# 1_P1.net
KiCad netlist of a schematic drawn in Altium Designer
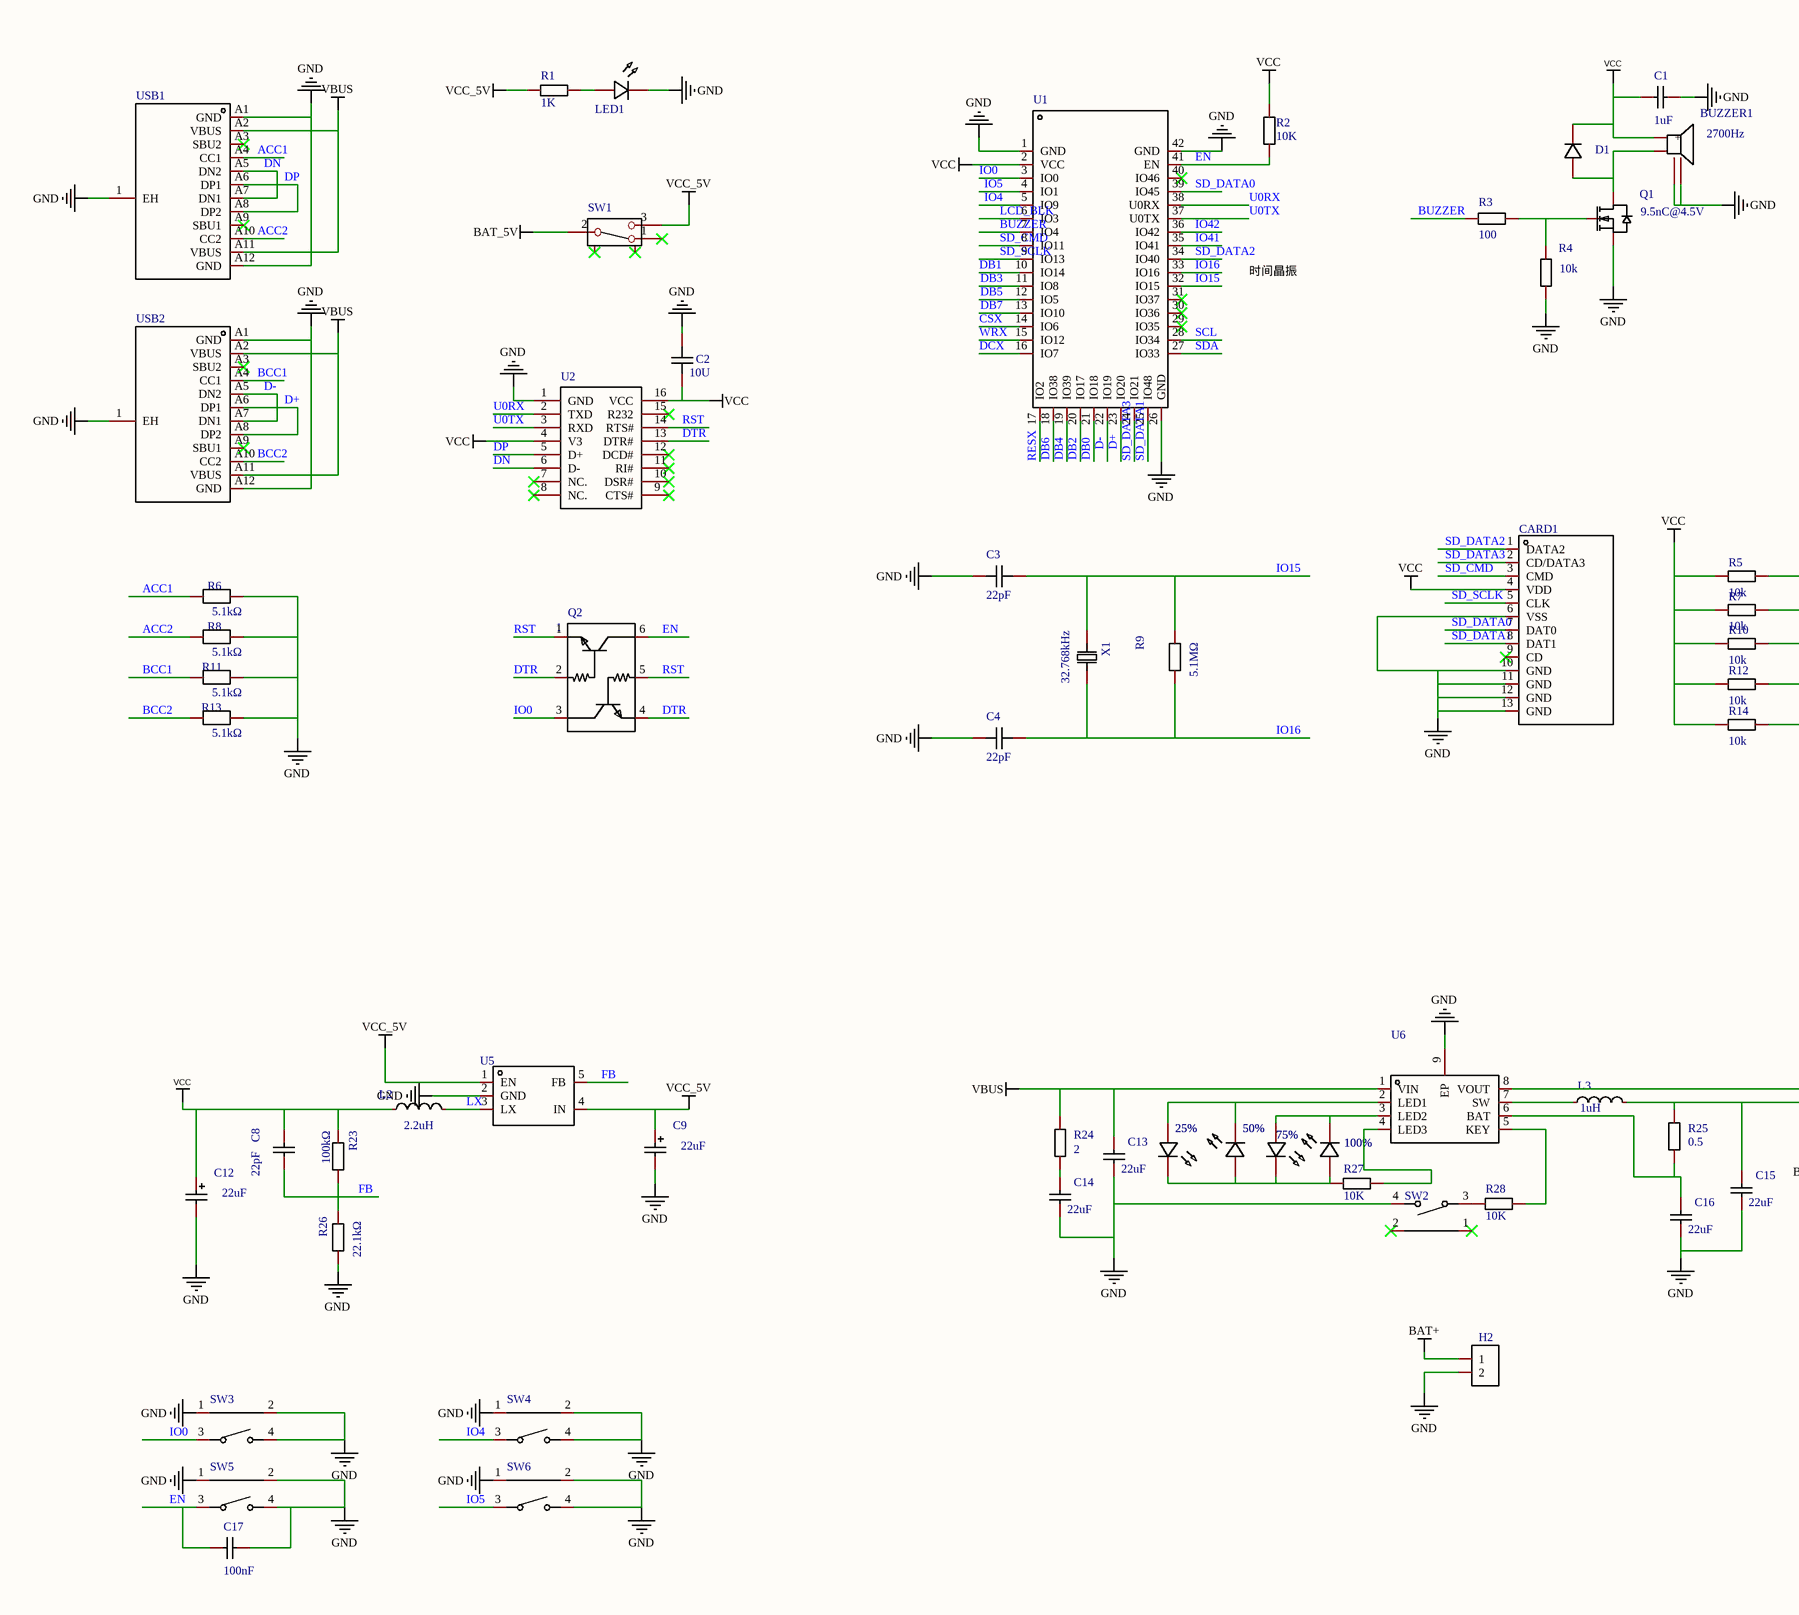
[diagram p0: 1_P1.schdoc, left]
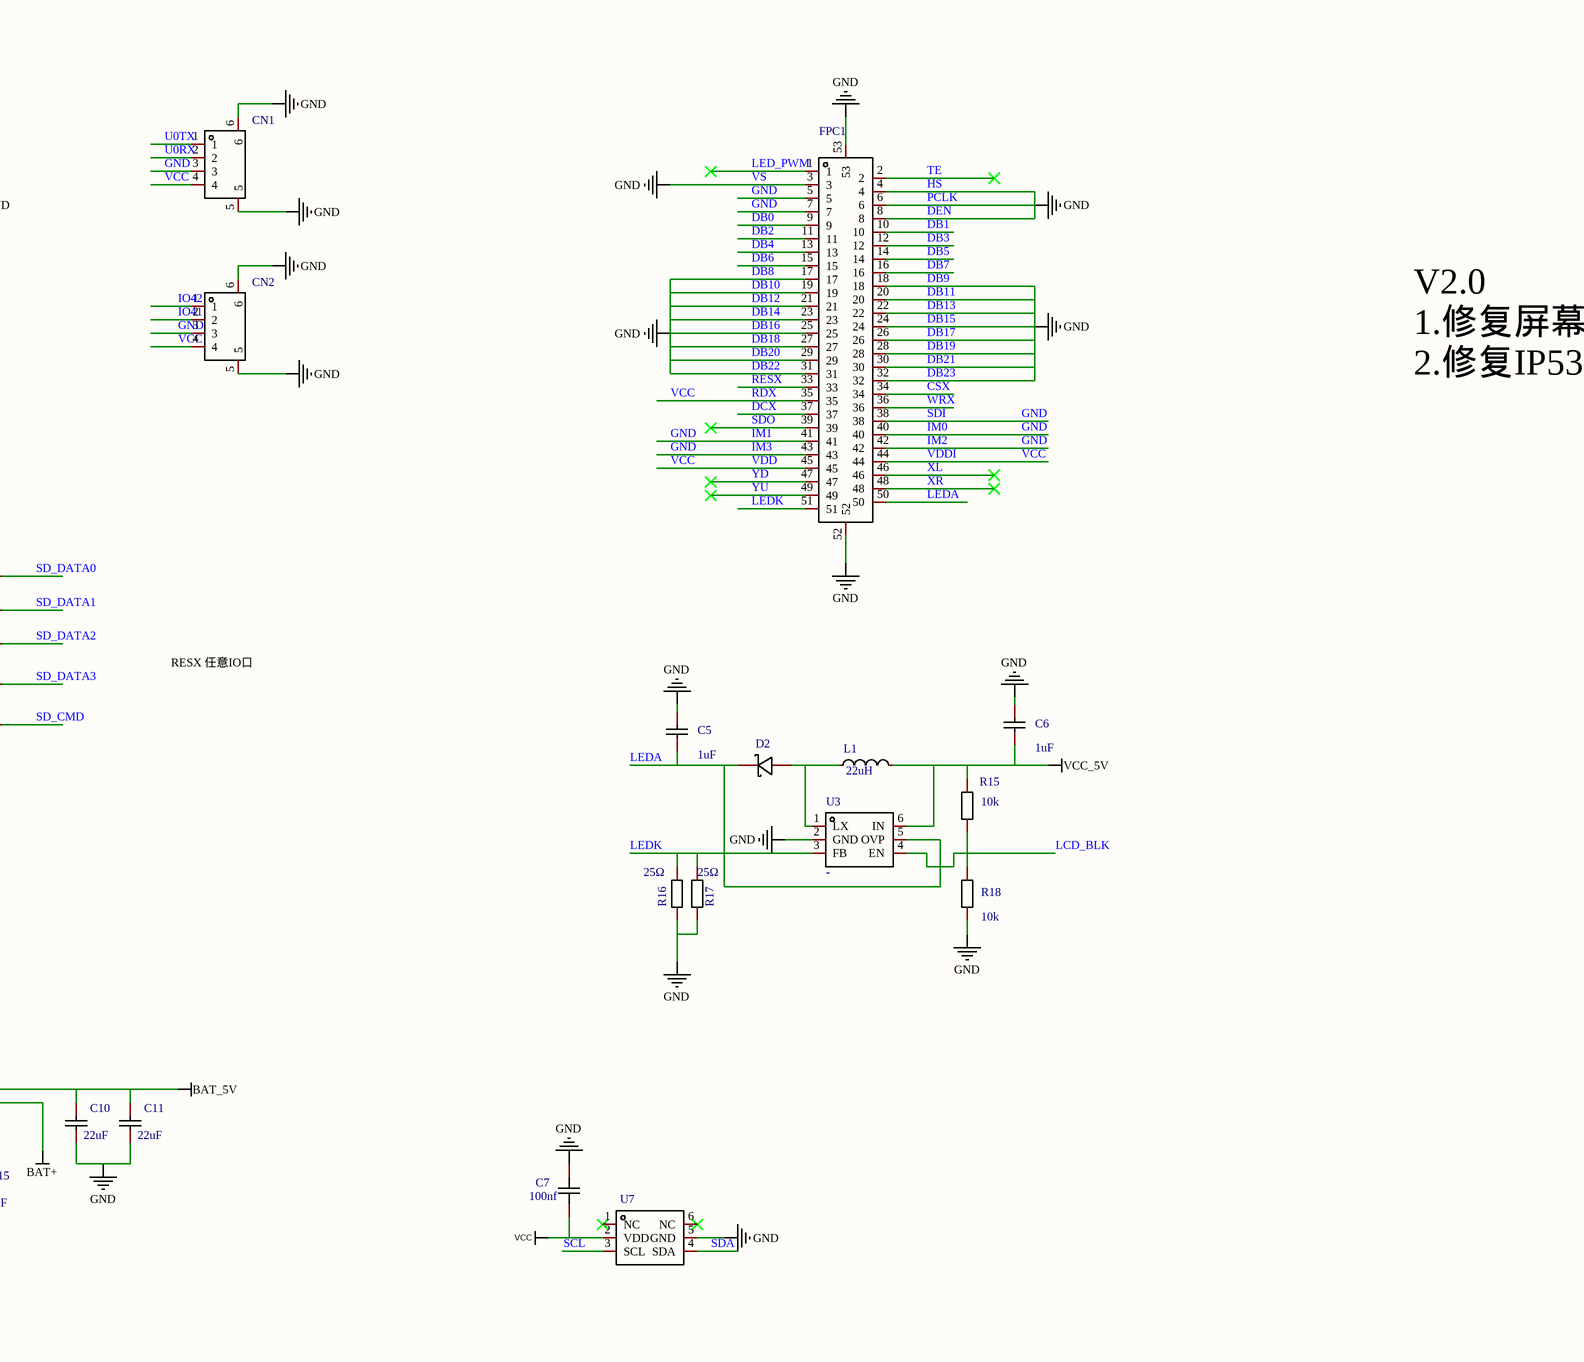
[diagram p1: 1_P1.schdoc, right]

(export (version "E")
  (design (tool "Eeschema 10.0.6"))
  (components
    (comp (ref "BUZZER1")
      (value "2700Hz")
      (fields (field (name "MANUFACTURER") "华能") (field (name "MANUFACTURER PART") "MLT-8530"))
      (libsource (lib "altium-import") (part "root_0_MLT-8530_"))
    )
    (comp (ref "C1")
      (value "1uF")
      (description "容值:1uF;精度:±10%;额定电压:16V;温度系数:X5R;")
      (fields
        (field (name "MANUFACTURER") "SAMSUNG(三星)")
        (field (name "MANUFACTURER PART") "CL10A105KO8NNNC")
      )
      (libsource (lib "altium-import") (part "root_0_CL10A105KO8NNNC_"))
    )
    (comp (ref "C2")
      (value "10U")
      (description "容值:100nF;精度:±10%;额定电压:50V;温度系数:X7R;")
      (fields (field (name "Comment") "CAP_0603"))
      (libsource (lib "altium-import") (part "root_1_CAP_0603_"))
    )
    (comp (ref "C3")
      (value "22pF")
      (description "容值:100nF;精度:±10%;额定电压:50V;温度系数:X7R;")
      (fields (field (name "Comment") "CAP_0603"))
      (libsource (lib "altium-import") (part "root_0_CAP_0603_"))
    )
    (comp (ref "C4")
      (value "22pF")
      (description "容值:100nF;精度:±10%;额定电压:50V;温度系数:X7R;")
      (fields (field (name "Comment") "CAP_0603"))
      (libsource (lib "altium-import") (part "root_0_CAP_0603_"))
    )
    (comp (ref "C5")
      (value "1uF")
      (description "容值:1uF;精度:±10%;额定电压:16V;温度系数:X5R;")
      (fields
        (field (name "MANUFACTURER") "SAMSUNG(三星)")
        (field (name "MANUFACTURER PART") "CL10A105KO8NNNC")
      )
      (libsource (lib "altium-import") (part "root_1_CL10A105KO8NNNC_"))
    )
    (comp (ref "C6")
      (value "1uF")
      (description "容值:1uF;精度:±10%;额定电压:16V;温度系数:X5R;")
      (fields
        (field (name "MANUFACTURER") "SAMSUNG(三星)")
        (field (name "MANUFACTURER PART") "CL10A105KO8NNNC")
      )
      (libsource (lib "altium-import") (part "root_1_CL10A105KO8NNNC_"))
    )
    (comp (ref "C7")
      (value "100nf")
      (description "容值:100nF;精度:±10%;额定电压:50V;温度系数:X7R;")
      (fields (field (name "Comment") "CAP_0603"))
      (libsource (lib "altium-import") (part "root_3_CAP_0603_"))
    )
    (comp (ref "C8")
      (value "22pF")
      (description "容值:22pF;精度:±5%;额定电压:50V;温度系数:NP0;")
      (fields
        (field (name "MANUFACTURER") "YAGEO(国巨)")
        (field (name "MANUFACTURER PART") "CC0603JRNPO9BN220")
      )
      (libsource (lib "altium-import") (part "root_1_cc0603jrnpo9bn220_"))
    )
    (comp (ref "C9")
      (value "22uF")
      (description "容值:22uF;精度:±10%;额定电压:16V;等效串联电阻:2.3Ω@100kHz;工作温度:-55~+125;")
      (fields (field (name "MANUFACTURER") "Kyocera AVX") (field (name "MANUFACTURER PART") "TAJB226K016RNJ"))
      (libsource (lib "altium-import") (part "root_1_TAJB226K016RNJ_"))
    )
    (comp (ref "C10")
      (value "22uF")
      (description "容值:1uF;精度:±10%;额定电压:16V;温度系数:X5R;")
      (fields
        (field (name "MANUFACTURER") "SAMSUNG(三星)")
        (field (name "MANUFACTURER PART") "CL10A105KO8NNNC")
      )
      (libsource (lib "altium-import") (part "root_1_CL10A105KO8NNNC_"))
    )
    (comp (ref "C11")
      (value "22uF")
      (description "容值:1uF;精度:±10%;额定电压:16V;温度系数:X5R;")
      (fields
        (field (name "MANUFACTURER") "SAMSUNG(三星)")
        (field (name "MANUFACTURER PART") "CL10A105KO8NNNC")
      )
      (libsource (lib "altium-import") (part "root_1_CL10A105KO8NNNC_"))
    )
    (comp (ref "C12")
      (value "22uF")
      (description "容值:22uF;精度:±10%;额定电压:16V;等效串联电阻:2.3Ω@100kHz;工作温度:-55~+125;")
      (fields (field (name "MANUFACTURER") "Kyocera AVX") (field (name "MANUFACTURER PART") "TAJB226K016RNJ"))
      (libsource (lib "altium-import") (part "root_1_TAJB226K016RNJ_"))
    )
    (comp (ref "C13")
      (value "22uF")
      (description "容值:1uF;精度:±10%;额定电压:16V;温度系数:X5R;")
      (fields
        (field (name "MANUFACTURER") "SAMSUNG(三星)")
        (field (name "MANUFACTURER PART") "CL10A105KO8NNNC")
      )
      (libsource (lib "altium-import") (part "root_1_CL10A105KO8NNNC_"))
    )
    (comp (ref "C14")
      (value "22uF")
      (description "容值:1uF;精度:±10%;额定电压:16V;温度系数:X5R;")
      (fields
        (field (name "MANUFACTURER") "SAMSUNG(三星)")
        (field (name "MANUFACTURER PART") "CL10A105KO8NNNC")
      )
      (libsource (lib "altium-import") (part "root_1_CL10A105KO8NNNC_"))
    )
    (comp (ref "C15")
      (value "22uF")
      (description "容值:1uF;精度:±10%;额定电压:16V;温度系数:X5R;")
      (fields
        (field (name "MANUFACTURER") "SAMSUNG(三星)")
        (field (name "MANUFACTURER PART") "CL10A105KO8NNNC")
      )
      (libsource (lib "altium-import") (part "root_1_CL10A105KO8NNNC_"))
    )
    (comp (ref "C16")
      (value "22uF")
      (description "容值:1uF;精度:±10%;额定电压:16V;温度系数:X5R;")
      (fields
        (field (name "MANUFACTURER") "SAMSUNG(三星)")
        (field (name "MANUFACTURER PART") "CL10A105KO8NNNC")
      )
      (libsource (lib "altium-import") (part "root_1_CL10A105KO8NNNC_"))
    )
    (comp (ref "C17")
      (value "100nF")
      (description "容值:100nF;精度:±10%;额定电压:50V;温度系数:X7R;")
      (fields (field (name "MANUFACTURER") "FH(风华)") (field (name "MANUFACTURER PART") "0603B104K500NT"))
      (libsource (lib "altium-import") (part "root_0_0603B104K500NT_"))
    )
    (comp (ref "CARD1")
      (value "tf-115-bcp9")
      (description "卡连接方式:自弹式;卡类型:MicroSD卡(TF卡);连接器类型:卡座;本体最大高度:1.80mm;触头材质:磷铜;触头镀层:银;工作温度范围:-25~+85;焊接温度(最大值):260;")
      (fields (field (name "MANUFACTURER") "XUNPU(讯普)") (field (name "MANUFACTURER PART") "TF-115-BCP9"))
      (libsource (lib "altium-import") (part "root_0_tf-115-bcp9_"))
    )
    (comp (ref "CN1")
      (value "PH-4P卧贴")
      (description "参考系列:PH;间距:2mm;插针结构:1x4P;排数:1;每排PIN数:4;行距:-;安装方式:-;触头材质:-;")
      (fields (field (name "MANUFACTURER") "BOOMELE(博穆精密)"))
      (libsource (lib "altium-import") (part "root_0_PH-4P卧贴_"))
    )
    (comp (ref "CN2")
      (value "PH-4P卧贴")
      (description "参考系列:PH;间距:2mm;插针结构:1x4P;排数:1;每排PIN数:4;行距:-;安装方式:-;触头材质:-;")
      (fields (field (name "MANUFACTURER") "BOOMELE(博穆精密)"))
      (libsource (lib "altium-import") (part "root_0_PH-4P卧贴_"))
    )
    (comp (ref "D1")
      (value "1N4148W")
      (fields (field (name "MANUFACTURER") "MDD"))
      (libsource (lib "altium-import") (part "root_3_1N4148W_"))
    )
    (comp (ref "D2")
      (value "SS34")
      (description "40V,3A,VF=0.55V 3A")
      (fields (field (name "MANUFACTURER") "MDD"))
      (libsource (lib "altium-import") (part "root_0_SS34_"))
    )
    (comp (ref "FPC1")
      (value "FH26W-51S-0.3SHW(60)")
      (description "间距:0.3mm;触点数量:51;锁定特性:翻盖式;安装类型:卧贴;触点类型:下接;")
      (fields (field (name "MANUFACTURER") "HRS(广濑)"))
      (libsource (lib "altium-import") (part "root_0_FH26W-51S-0.3SHW(60)_"))
    )
    (comp (ref "H2")
      (value "HDR-F_2.54_1x2P")
      (libsource (lib "altium-import") (part "root_0_HDR-F_2.54_1x2P_"))
    )
    (comp (ref "L1")
      (value "22uH")
      (description "额定电流:1.5A;精度:±20%;直流电阻(DCR):168mΩ;电感值:22uH;")
      (fields (field (name "MANUFACTURER") "Sunlord(顺络)") (field (name "MANUFACTURER PART") "SWPA5040S220MT"))
      (libsource (lib "altium-import") (part "root_0_SWPA5040S220MT_"))
    )
    (comp (ref "L2")
      (value "2.2uH")
      (description "电感值:2.2uH;精度:±20%;额定电流:3A;直流电阻(DCR):42m;")
      (fields
        (field (name "MANUFACTURER") "Sunltech(韩国顺磁)")
        (field (name "MANUFACTURER PART") "SLO0420H2R2MTT")
      )
      (libsource (lib "altium-import") (part "root_0_SLO0420H2R2MTT_"))
    )
    (comp (ref "L3")
      (value "1uH")
      (description "直流电阻(DCR):7.81mΩ;精度:±20%;电感值:1uH;额定电流:13A;")
      (fields (field (name "MANUFACTURER") "TDK") (field (name "MANUFACTURER PART") "SPM6530T-1R0M120"))
      (libsource (lib "altium-import") (part "root_0_SPM6530T-1R0M120_"))
    )
    (comp (ref "LED1") (value "LED_0603-R") (libsource (lib "altium-import") (part "root_0_LED_0603-R_")))
    (comp (ref "LED4")
      (value "100%")
      (fields (field (name "NAME") "100%"))
      (libsource (lib "altium-import") (part "root_1_LED_0603-R_"))
    )
    (comp (ref "LED5")
      (value "25%")
      (fields (field (name "NAME") "25%"))
      (libsource (lib "altium-import") (part "root_3_LED_0603-R_"))
    )
    (comp (ref "LED6")
      (value "50%")
      (fields (field (name "NAME") "50%"))
      (libsource (lib "altium-import") (part "root_1_LED_0603-R_"))
    )
    (comp (ref "LED7")
      (value "75%")
      (fields (field (name "NAME") "75%"))
      (libsource (lib "altium-import") (part "root_3_LED_0603-R_"))
    )
    (comp (ref "Q1")
      (value "AO3400")
      (fields
        (field (name "MANUFACTURER") "LGE(鲁光)")
        (field (name "TOTAL GATE CHARGE (QG@VGS)") "9.5nC@4.5V")
      )
      (libsource (lib "altium-import") (part "root_0_AO3400_"))
    )
    (comp (ref "Q2")
      (value "UMH3N")
      (description "晶体管类型:2个NPN-预偏置;功率(Pd):150mW;集电极电流(Ic):100mA;集射极击穿电压(Vceo):50V;")
      (fields (field (name "MANUFACTURER") "CJ(江苏长电/长晶)") (field (name "NUMBER") "1"))
      (libsource (lib "altium-import") (part "root_3_UMH3N_"))
    )
    (comp (ref "R1")
      (value "1K")
      (fields (field (name "Comment") "Res_0603"))
      (libsource (lib "altium-import") (part "root_2_Res_0603_"))
    )
    (comp (ref "R2")
      (value "10K")
      (fields (field (name "Comment") "Res_0603"))
      (libsource (lib "altium-import") (part "root_1_Res_0603_"))
    )
    (comp (ref "R3")
      (value "100")
      (description "电阻类型:厚膜电阻;阻值:100;精度:±1%;功率:100mW;温度系数:±100ppm/;最大工作电压:75V;工作温度范围:-55~+155;")
      (fields (field (name "MANUFACTURER") "YAGEO(国巨)") (field (name "MANUFACTURER PART") "RC0603FR-07100RL"))
      (libsource (lib "altium-import") (part "root_0_RC0603FR-07100RL_"))
    )
    (comp (ref "R4")
      (value "10k")
      (description "阻值:10k;精度:±1%;功率:100mW;温度系数:±100ppm/;最大工作电压:75V;工作温度范围:-55~+155;")
      (fields (field (name "MANUFACTURER") "YAGEO(国巨)") (field (name "MANUFACTURER PART") "RC0603FR-0710KL"))
      (libsource (lib "altium-import") (part "root_1_RC0603FR-0710KL_1_"))
    )
    (comp (ref "R5")
      (value "10k")
      (description "电阻类型:厚膜电阻;阻值:10k;精度:±1%;功率:1/10W;温度系数:±100ppm/;最大工作电压:75V;工作温度范围:-55~+155;")
      (fields
        (field (name "MANUFACTURER") "UNI-ROYAL(厚声)")
        (field (name "MANUFACTURER PART") "0603WAF1002T5E")
      )
      (libsource (lib "altium-import") (part "root_0_0603waf1002t5e_"))
    )
    (comp (ref "R6")
      (value "5.1kΩ")
      (description "温度系数:±25ppm/℃;精度:±0.1%;功率:100mW;阻值:5.1kΩ;最大工作电压:50V;工作温度范围:-55℃~+155℃;")
      (fields (field (name "MANUFACTURER") "FH(风华)") (field (name "MANUFACTURER PART") "TD03G5101BT"))
      (libsource (lib "altium-import") (part "root_2_td03g5101bt_"))
    )
    (comp (ref "R7")
      (value "10k")
      (description "电阻类型:厚膜电阻;阻值:10k;精度:±1%;功率:1/10W;温度系数:±100ppm/;最大工作电压:75V;工作温度范围:-55~+155;")
      (fields
        (field (name "MANUFACTURER") "UNI-ROYAL(厚声)")
        (field (name "MANUFACTURER PART") "0603WAF1002T5E")
      )
      (libsource (lib "altium-import") (part "root_0_0603waf1002t5e_"))
    )
    (comp (ref "R8")
      (value "5.1kΩ")
      (description "温度系数:±25ppm/℃;精度:±0.1%;功率:100mW;阻值:5.1kΩ;最大工作电压:50V;工作温度范围:-55℃~+155℃;")
      (fields (field (name "MANUFACTURER") "FH(风华)") (field (name "MANUFACTURER PART") "TD03G5101BT"))
      (libsource (lib "altium-import") (part "root_2_td03g5101bt_"))
    )
    (comp (ref "R9")
      (value "5.1MΩ")
      (description "电阻类型:厚膜电阻;阻值:5.1MΩ;精度:±5%;功率:1/10W;温度系数:±100ppm/℃;最大工作电压:75V;工作温度范围:-55℃~+155℃;")
      (fields
        (field (name "MANUFACTURER") "UNI-ROYAL(厚声)")
        (field (name "MANUFACTURER PART") "0603WAJ0515T5E")
      )
      (libsource (lib "altium-import") (part "root_1_0603WAJ0515T5E_"))
    )
    (comp (ref "R10")
      (value "10k")
      (description "电阻类型:厚膜电阻;阻值:10k;精度:±1%;功率:1/10W;温度系数:±100ppm/;最大工作电压:75V;工作温度范围:-55~+155;")
      (fields
        (field (name "MANUFACTURER") "UNI-ROYAL(厚声)")
        (field (name "MANUFACTURER PART") "0603WAF1002T5E")
      )
      (libsource (lib "altium-import") (part "root_0_0603waf1002t5e_"))
    )
    (comp (ref "R11")
      (value "5.1kΩ")
      (description "温度系数:±25ppm/℃;精度:±0.1%;功率:100mW;阻值:5.1kΩ;最大工作电压:50V;工作温度范围:-55℃~+155℃;")
      (fields (field (name "MANUFACTURER") "FH(风华)") (field (name "MANUFACTURER PART") "TD03G5101BT"))
      (libsource (lib "altium-import") (part "root_2_td03g5101bt_"))
    )
    (comp (ref "R12")
      (value "10k")
      (description "电阻类型:厚膜电阻;阻值:10k;精度:±1%;功率:1/10W;温度系数:±100ppm/;最大工作电压:75V;工作温度范围:-55~+155;")
      (fields
        (field (name "MANUFACTURER") "UNI-ROYAL(厚声)")
        (field (name "MANUFACTURER PART") "0603WAF1002T5E")
      )
      (libsource (lib "altium-import") (part "root_0_0603waf1002t5e_"))
    )
    (comp (ref "R13")
      (value "5.1kΩ")
      (description "温度系数:±25ppm/℃;精度:±0.1%;功率:100mW;阻值:5.1kΩ;最大工作电压:50V;工作温度范围:-55℃~+155℃;")
      (fields (field (name "MANUFACTURER") "FH(风华)") (field (name "MANUFACTURER PART") "TD03G5101BT"))
      (libsource (lib "altium-import") (part "root_2_td03g5101bt_"))
    )
    (comp (ref "R14")
      (value "10k")
      (description "电阻类型:厚膜电阻;阻值:10k;精度:±1%;功率:1/10W;温度系数:±100ppm/;最大工作电压:75V;工作温度范围:-55~+155;")
      (fields
        (field (name "MANUFACTURER") "UNI-ROYAL(厚声)")
        (field (name "MANUFACTURER PART") "0603WAF1002T5E")
      )
      (libsource (lib "altium-import") (part "root_0_0603waf1002t5e_"))
    )
    (comp (ref "R15")
      (value "10k")
      (description "阻值:10k;精度:±1%;功率:100mW;温度系数:±100ppm/;最大工作电压:75V;工作温度范围:-55~+155;")
      (fields (field (name "MANUFACTURER") "YAGEO(国巨)") (field (name "MANUFACTURER PART") "RC0603FR-0710KL"))
      (libsource (lib "altium-import") (part "root_1_RC0603FR-0710KL_1_"))
    )
    (comp (ref "R16")
      (value "25Ω")
      (description "阻值:10k;精度:±1%;功率:100mW;温度系数:±100ppm/;最大工作电压:75V;工作温度范围:-55~+155;")
      (fields (field (name "MANUFACTURER") "YAGEO(国巨)") (field (name "MANUFACTURER PART") "RC0603FR-0710KL"))
      (libsource (lib "altium-import") (part "root_1_RC0603FR-0710KL_1_"))
    )
    (comp (ref "R17")
      (value "25Ω")
      (description "阻值:10k;精度:±1%;功率:100mW;温度系数:±100ppm/;最大工作电压:75V;工作温度范围:-55~+155;")
      (fields (field (name "MANUFACTURER") "YAGEO(国巨)") (field (name "MANUFACTURER PART") "RC0603FR-0710KL"))
      (libsource (lib "altium-import") (part "root_1_RC0603FR-0710KL_1_"))
    )
    (comp (ref "R18")
      (value "10k")
      (description "阻值:10k;精度:±1%;功率:100mW;温度系数:±100ppm/;最大工作电压:75V;工作温度范围:-55~+155;")
      (fields (field (name "MANUFACTURER") "YAGEO(国巨)") (field (name "MANUFACTURER PART") "RC0603FR-0710KL"))
      (libsource (lib "altium-import") (part "root_1_RC0603FR-0710KL_1_"))
    )
    (comp (ref "R23")
      (value "100kΩ")
      (description "阻值:100kΩ;精度:±1%;功率:100mW;温度系数:±100ppm/℃;最大工作电压:75V;工作温度范围:-55℃~+155℃;")
      (fields (field (name "MANUFACTURER") "YAGEO(国巨)") (field (name "MANUFACTURER PART") "RC0603FR-07100KL"))
      (libsource (lib "altium-import") (part "root_3_rc0603fr-07100kl_"))
    )
    (comp (ref "R24")
      (value "2")
      (description "电阻类型:厚膜电阻;阻值:10k;精度:±1%;功率:1/10W;温度系数:±100ppm/;最大工作电压:75V;工作温度范围:-55~+155;")
      (fields
        (field (name "MANUFACTURER") "UNI-ROYAL(厚声)")
        (field (name "MANUFACTURER PART") "0603WAF1002T5E")
      )
      (libsource (lib "altium-import") (part "root_1_0603waf1002t5e_"))
    )
    (comp (ref "R25")
      (value "0.5")
      (description "电阻类型:厚膜电阻;阻值:10k;精度:±1%;功率:1/10W;温度系数:±100ppm/;最大工作电压:75V;工作温度范围:-55~+155;")
      (fields
        (field (name "MANUFACTURER") "UNI-ROYAL(厚声)")
        (field (name "MANUFACTURER PART") "0603WAF1002T5E")
      )
      (libsource (lib "altium-import") (part "root_3_0603waf1002t5e_"))
    )
    (comp (ref "R26")
      (value "22.1kΩ")
      (description "电阻类型:厚膜电阻;阻值:22.1kΩ;精度:±1%;功率:1/10W;温度系数:±100ppm/℃;最大工作电压:75V;工作温度范围:-55℃~+155℃;")
      (fields
        (field (name "MANUFACTURER") "UNI-ROYAL(厚声)")
        (field (name "MANUFACTURER PART") "0603WAF2212T5E")
      )
      (libsource (lib "altium-import") (part "root_1_0603waf2212t5e_"))
    )
    (comp (ref "R27")
      (value "10K")
      (description "电阻类型:厚膜电阻;阻值:10k;精度:±1%;功率:1/10W;温度系数:±100ppm/;最大工作电压:75V;工作温度范围:-55~+155;")
      (fields
        (field (name "MANUFACTURER") "UNI-ROYAL(厚声)")
        (field (name "MANUFACTURER PART") "0603WAF1002T5E")
      )
      (libsource (lib "altium-import") (part "root_2_0603waf1002t5e_"))
    )
    (comp (ref "R28")
      (value "10K")
      (description "电阻类型:厚膜电阻;阻值:10k;精度:±1%;功率:1/10W;温度系数:±100ppm/;最大工作电压:75V;工作温度范围:-55~+155;")
      (fields
        (field (name "MANUFACTURER") "UNI-ROYAL(厚声)")
        (field (name "MANUFACTURER PART") "0603WAF1002T5E")
      )
      (libsource (lib "altium-import") (part "root_2_0603waf1002t5e_"))
    )
    (comp (ref "SW1")
      (value "SK-12D02-VG5")
      (fields (field (name "MANUFACTURER") "韩国韩荣"))
      (libsource (lib "altium-import") (part "root_0_SK-12D02-VG5_"))
    )
    (comp (ref "SW2")
      (value "TS24CA")
      (description "触点电流:50mA;额定电压(DC):12V;电路结构:单刀单掷;安装方式:卧贴;按钮形状:矩形按钮;带灯:-;开关长度:4.55mm;开关宽度:1.8mm;开关高度:3.5mm;")
      (fields (field (name "MANUFACTURER") "SHOU HAN(首韩)"))
      (libsource (lib "altium-import") (part "root_2_TS24CA_"))
    )
    (comp (ref "SW3")
      (value "TS24CA")
      (description "触点电流:50mA;额定电压(DC):12V;电路结构:单刀单掷;安装方式:卧贴;按钮形状:矩形按钮;带灯:-;开关长度:4.55mm;开关宽度:1.8mm;开关高度:3.5mm;")
      (fields (field (name "MANUFACTURER") "SHOU HAN(首韩)"))
      (libsource (lib "altium-import") (part "root_0_TS24CA_"))
    )
    (comp (ref "SW4")
      (value "TS24CA")
      (description "触点电流:50mA;额定电压(DC):12V;电路结构:单刀单掷;安装方式:卧贴;按钮形状:矩形按钮;带灯:-;开关长度:4.55mm;开关宽度:1.8mm;开关高度:3.5mm;")
      (fields (field (name "MANUFACTURER") "SHOU HAN(首韩)"))
      (libsource (lib "altium-import") (part "root_0_TS24CA_"))
    )
    (comp (ref "SW5")
      (value "TS24CA")
      (description "触点电流:50mA;额定电压(DC):12V;电路结构:单刀单掷;安装方式:卧贴;按钮形状:矩形按钮;带灯:-;开关长度:4.55mm;开关宽度:1.8mm;开关高度:3.5mm;")
      (fields (field (name "MANUFACTURER") "SHOU HAN(首韩)"))
      (libsource (lib "altium-import") (part "root_0_TS24CA_"))
    )
    (comp (ref "SW6")
      (value "TS24CA")
      (description "触点电流:50mA;额定电压(DC):12V;电路结构:单刀单掷;安装方式:卧贴;按钮形状:矩形按钮;带灯:-;开关长度:4.55mm;开关宽度:1.8mm;开关高度:3.5mm;")
      (fields (field (name "MANUFACTURER") "SHOU HAN(首韩)"))
      (libsource (lib "altium-import") (part "root_0_TS24CA_"))
    )
    (comp (ref "U1") (value "ESP-S3-12K") (libsource (lib "altium-import") (part "root_0_ESP-S3-12K_")))
    (comp (ref "U2")
      (value "CH340C")
      (description "类型:Transceiver;协议类别:USB 2.0;驱动器/接收器数:-;数据速率:2Mbps;")
      (fields (field (name "MANUFACTURER") "WCH(南京沁恒)"))
      (libsource (lib "altium-import") (part "root_0_CH340C_"))
    )
    (comp (ref "U3")
      (value "-")
      (description "类型:-;拓扑结构:-;内部开关:-;供电电压（最低）:-;供电电压（最高）:-;频率:-;")
      (fields (field (name "MANUFACTURER") "RYCHiP(蕊源)") (field (name "MANUFACTURER PART") "RY3730"))
      (libsource (lib "altium-import") (part "root_0_RY3730_"))
    )
    (comp (ref "U5")
      (value "sy8088aac")
      (description "功能类型:降压型;同步整流:-;输出通道数:-;拓扑结构:-;输入电压:-;输出电流(最大值):-;开关频率:-;")
      (fields (field (name "MANUFACTURER") "矽力杰silergy") (field (name "MANUFACTURER PART") "3."))
      (libsource (lib "altium-import") (part "root_0_sy8088aac_"))
    )
    (comp (ref "U6")
      (value "IP5306")
      (description "充电电池的类型:-;电池单元组数:-;最大充电电流:-;充满的电池组电压:-;最大供应电压:-;")
      (fields (field (name "MANUFACTURER") "INJOINIC(英集芯)"))
      (libsource (lib "altium-import") (part "root_0_IP5306_"))
    )
    (comp (ref "U7")
      (value "AHT20")
      (fields (field (name "MANUFACTURER") "广州奥松"))
      (libsource (lib "altium-import") (part "root_0_AHT20_"))
    )
    (comp (ref "USB1")
      (value "TYPE-C-2.0-16PIN-SMT-3")
      (description "连接器类型:Type-C;标准:USB 2.0;公母:母座;触点数量:16;端口数量:1;安装方式:卧贴;额定电流 - 电源:3A;工作温度范围:-40~+85;")
      (fields (field (name "MANUFACTURER") "CIKI(皓富)"))
      (libsource (lib "altium-import") (part "root_0_mirrored_TYPE-C-2.0-16PIN-SMT-3_"))
    )
    (comp (ref "USB2")
      (value "TYPE-C-2.0-16PIN-SMT-3")
      (description "连接器类型:Type-C;标准:USB 2.0;公母:母座;触点数量:16;端口数量:1;安装方式:卧贴;额定电流 - 电源:3A;工作温度范围:-40~+85;")
      (fields (field (name "MANUFACTURER") "CIKI(皓富)"))
      (libsource (lib "altium-import") (part "root_0_mirrored_TYPE-C-2.0-16PIN-SMT-3_"))
    )
    (comp (ref "X1")
      (value "32.768kHz")
      (description "晶振类型:贴片无源晶振;频率:32.768kHz;频率公差:±20ppm;频率稳定度:-;负载电容:12.5pF;等效串联电阻(ESR):70kΩ;工作温度:-40℃~+85℃;")
      (fields (field (name "MANUFACTURER") "EPSON(爱普生)") (field (name "MANUFACTURER PART") "Q13FC1350000400"))
      (libsource (lib "altium-import") (part "root_1_Q13FC1350000400_"))
    )
  )
  (nets
    (net (code "1") (name "/ACC1") (class "Default")
      (node (ref "R6") (pin "2") (pinfunction "2_2") (pintype "passive"))
      (node (ref "USB1") (pin "A4") (pinfunction "CC1_A4") (pintype "passive"))
    )
    (net (code "2") (name "/ACC2") (class "Default")
      (node (ref "R8") (pin "2") (pinfunction "2_2") (pintype "passive"))
      (node (ref "USB1") (pin "A10") (pinfunction "CC2_A10") (pintype "passive"))
    )
    (net (code "3") (name "/BCC1") (class "Default")
      (node (ref "R11") (pin "2") (pinfunction "2_2") (pintype "passive"))
      (node (ref "USB2") (pin "A4") (pinfunction "CC1_A4") (pintype "passive"))
    )
    (net (code "4") (name "/BCC2") (class "Default")
      (node (ref "R13") (pin "2") (pinfunction "2_2") (pintype "passive"))
      (node (ref "USB2") (pin "A10") (pinfunction "CC2_A10") (pintype "passive"))
    )
    (net (code "5") (name "/BUZZER") (class "Default")
      (node (ref "R3") (pin "1") (pinfunction "1_1") (pintype "passive"))
      (node (ref "U1") (pin "7") (pinfunction "IO4_7") (pintype "passive"))
    )
    (net (code "6") (name "/CSX") (class "Default")
      (node (ref "FPC1") (pin "34") (pinfunction "34_34") (pintype "passive"))
      (node (ref "U1") (pin "14") (pinfunction "IO6_14") (pintype "passive"))
    )
    (net (code "7") (name "/D+") (class "Default")
      (node (ref "U1") (pin "23") (pinfunction "IO20_23") (pintype "passive"))
      (node (ref "USB2") (pin "A6") (pinfunction "DP1_A6") (pintype "passive"))
      (node (ref "USB2") (pin "A8") (pinfunction "DP2_A8") (pintype "passive"))
    )
    (net (code "8") (name "/D-") (class "Default")
      (node (ref "U1") (pin "22") (pinfunction "IO19_22") (pintype "passive"))
      (node (ref "USB2") (pin "A5") (pinfunction "DN2_A5") (pintype "passive"))
      (node (ref "USB2") (pin "A7") (pinfunction "DN1_A7") (pintype "passive"))
    )
    (net (code "9") (name "/DB0") (class "Default")
      (node (ref "FPC1") (pin "9") (pinfunction "9_9") (pintype "passive"))
      (node (ref "U1") (pin "21") (pinfunction "IO18_21") (pintype "passive"))
    )
    (net (code "10") (name "/DB1") (class "Default")
      (node (ref "FPC1") (pin "10") (pinfunction "10_10") (pintype "passive"))
      (node (ref "U1") (pin "10") (pinfunction "IO14_10") (pintype "passive"))
    )
    (net (code "11") (name "/DB2") (class "Default")
      (node (ref "FPC1") (pin "11") (pinfunction "11_11") (pintype "passive"))
      (node (ref "U1") (pin "20") (pinfunction "IO17_20") (pintype "passive"))
    )
    (net (code "12") (name "/DB3") (class "Default")
      (node (ref "FPC1") (pin "12") (pinfunction "12_12") (pintype "passive"))
      (node (ref "U1") (pin "11") (pinfunction "IO8_11") (pintype "passive"))
    )
    (net (code "13") (name "/DB4") (class "Default")
      (node (ref "FPC1") (pin "13") (pinfunction "13_13") (pintype "passive"))
      (node (ref "U1") (pin "19") (pinfunction "IO39_19") (pintype "passive"))
    )
    (net (code "14") (name "/DB5") (class "Default")
      (node (ref "FPC1") (pin "14") (pinfunction "14_14") (pintype "passive"))
      (node (ref "U1") (pin "12") (pinfunction "IO5_12") (pintype "passive"))
    )
    (net (code "15") (name "/DB6") (class "Default")
      (node (ref "FPC1") (pin "15") (pinfunction "15_15") (pintype "passive"))
      (node (ref "U1") (pin "18") (pinfunction "IO38_18") (pintype "passive"))
    )
    (net (code "16") (name "/DB7") (class "Default")
      (node (ref "FPC1") (pin "16") (pinfunction "16_16") (pintype "passive"))
      (node (ref "U1") (pin "13") (pinfunction "IO10_13") (pintype "passive"))
    )
    (net (code "17") (name "/DCX") (class "Default")
      (node (ref "FPC1") (pin "37") (pinfunction "37_37") (pintype "passive"))
      (node (ref "U1") (pin "16") (pinfunction "IO7_16") (pintype "passive"))
    )
    (net (code "18") (name "/DN") (class "Default")
      (node (ref "U2") (pin "6") (pinfunction "D-_6") (pintype "passive"))
      (node (ref "USB1") (pin "A5") (pinfunction "DN2_A5") (pintype "passive"))
      (node (ref "USB1") (pin "A7") (pinfunction "DN1_A7") (pintype "passive"))
    )
    (net (code "19") (name "/DP") (class "Default")
      (node (ref "U2") (pin "5") (pinfunction "D+_5") (pintype "passive"))
      (node (ref "USB1") (pin "A6") (pinfunction "DP1_A6") (pintype "passive"))
      (node (ref "USB1") (pin "A8") (pinfunction "DP2_A8") (pintype "passive"))
    )
    (net (code "20") (name "/DTR") (class "Default")
      (node (ref "Q2") (pin "2") (pinfunction "B_2") (pintype "passive"))
      (node (ref "Q2") (pin "4") (pinfunction "E_4") (pintype "passive"))
      (node (ref "U2") (pin "13") (pinfunction "DTR#_13") (pintype "passive"))
    )
    (net (code "21") (name "/EN") (class "Default")
      (node (ref "C17") (pin "1") (pinfunction "1_1") (pintype "passive"))
      (node (ref "Q2") (pin "6") (pinfunction "C_6") (pintype "passive"))
      (node (ref "R2") (pin "1") (pinfunction "1_1") (pintype "passive"))
      (node (ref "SW5") (pin "3") (pinfunction "3_3") (pintype "passive"))
      (node (ref "U1") (pin "41") (pinfunction "EN_41") (pintype "passive"))
    )
    (net (code "22") (name "/FB") (class "Default")
      (node (ref "C8") (pin "1") (pinfunction "1_1") (pintype "passive"))
      (node (ref "R23") (pin "2") (pinfunction "2_2") (pintype "passive"))
      (node (ref "R26") (pin "2") (pinfunction "2_2") (pintype "passive"))
      (node (ref "U5") (pin "5") (pinfunction "FB_5") (pintype "passive"))
    )
    (net (code "23") (name "/IO0") (class "Default")
      (node (ref "Q2") (pin "3") (pinfunction "C_3") (pintype "passive"))
      (node (ref "SW3") (pin "3") (pinfunction "3_3") (pintype "passive"))
      (node (ref "U1") (pin "3") (pinfunction "IO0_3") (pintype "passive"))
    )
    (net (code "24") (name "/IO4") (class "Default")
      (node (ref "SW4") (pin "3") (pinfunction "3_3") (pintype "passive"))
      (node (ref "U1") (pin "5") (pinfunction "IO9_5") (pintype "passive"))
    )
    (net (code "25") (name "/IO5") (class "Default")
      (node (ref "SW6") (pin "3") (pinfunction "3_3") (pintype "passive"))
      (node (ref "U1") (pin "4") (pinfunction "IO1_4") (pintype "passive"))
    )
    (net (code "26") (name "/IO15") (class "Default")
      (node (ref "C3") (pin "2") (pinfunction "2_2") (pintype "passive"))
      (node (ref "R9") (pin "2") (pinfunction "2_2") (pintype "passive"))
      (node (ref "U1") (pin "32") (pinfunction "IO15_32") (pintype "passive"))
      (node (ref "X1") (pin "2") (pinfunction "2_2") (pintype "passive"))
    )
    (net (code "27") (name "/IO16") (class "Default")
      (node (ref "C4") (pin "2") (pinfunction "2_2") (pintype "passive"))
      (node (ref "R9") (pin "1") (pinfunction "1_1") (pintype "passive"))
      (node (ref "U1") (pin "33") (pinfunction "IO16_33") (pintype "passive"))
      (node (ref "X1") (pin "1") (pinfunction "1_1") (pintype "passive"))
    )
    (net (code "28") (name "/IO41") (class "Default")
      (node (ref "CN2") (pin "2") (pinfunction "2_2") (pintype "passive"))
      (node (ref "U1") (pin "35") (pinfunction "IO41_35") (pintype "passive"))
    )
    (net (code "29") (name "/IO42") (class "Default")
      (node (ref "CN2") (pin "1") (pinfunction "1_1") (pintype "passive"))
      (node (ref "U1") (pin "36") (pinfunction "IO42_36") (pintype "passive"))
    )
    (net (code "30") (name "/LCD_BLK") (class "Default")
      (node (ref "R15") (pin "1") (pinfunction "1_1") (pintype "passive"))
      (node (ref "R18") (pin "2") (pinfunction "2_2") (pintype "passive"))
      (node (ref "U1") (pin "6") (pinfunction "IO3_6") (pintype "passive"))
      (node (ref "U3") (pin "4") (pinfunction "EN_4") (pintype "passive"))
    )
    (net (code "31") (name "/LEDA") (class "Default")
      (node (ref "C5") (pin "1") (pinfunction "1_1") (pintype "passive"))
      (node (ref "D2") (pin "1") (pinfunction "K_1") (pintype "passive"))
      (node (ref "FPC1") (pin "50") (pinfunction "50_50") (pintype "passive"))
      (node (ref "U3") (pin "5") (pinfunction "OVP_5") (pintype "passive"))
    )
    (net (code "32") (name "/LEDK") (class "Default")
      (node (ref "FPC1") (pin "51") (pinfunction "51_51") (pintype "passive"))
      (node (ref "R16") (pin "2") (pinfunction "2_2") (pintype "passive"))
      (node (ref "R17") (pin "2") (pinfunction "2_2") (pintype "passive"))
      (node (ref "U3") (pin "3") (pinfunction "FB_3") (pintype "passive"))
    )
    (net (code "33") (name "/LED_PWM") (class "Default")
      (node (ref "FPC1") (pin "1") (pinfunction "1_1") (pintype "passive+no_connect"))
    )
    (net (code "34") (name "/LX") (class "Default")
      (node (ref "L2") (pin "2") (pinfunction "2_2") (pintype "passive"))
      (node (ref "U5") (pin "3") (pinfunction "LX_3") (pintype "passive"))
    )
    (net (code "35") (name "/RESX") (class "Default")
      (node (ref "FPC1") (pin "33") (pinfunction "33_33") (pintype "passive"))
      (node (ref "U1") (pin "17") (pinfunction "IO2_17") (pintype "passive"))
    )
    (net (code "36") (name "/RST") (class "Default")
      (node (ref "Q2") (pin "1") (pinfunction "E_1") (pintype "passive"))
      (node (ref "Q2") (pin "5") (pinfunction "B_5") (pintype "passive"))
      (node (ref "U2") (pin "14") (pinfunction "RTS#_14") (pintype "passive"))
    )
    (net (code "37") (name "/SCL") (class "Default")
      (node (ref "U1") (pin "28") (pinfunction "IO34_28") (pintype "passive"))
      (node (ref "U7") (pin "3") (pinfunction "SCL_3") (pintype "passive"))
    )
    (net (code "38") (name "/SDA") (class "Default")
      (node (ref "U1") (pin "27") (pinfunction "IO33_27") (pintype "passive"))
      (node (ref "U7") (pin "4") (pinfunction "SDA_4") (pintype "passive"))
    )
    (net (code "39") (name "/SDO") (class "Default")
      (node (ref "FPC1") (pin "39") (pinfunction "39_39") (pintype "passive+no_connect"))
    )
    (net (code "40") (name "/SD_CMD") (class "Default")
      (node (ref "CARD1") (pin "3") (pinfunction "CMD_3") (pintype "passive"))
      (node (ref "R14") (pin "2") (pinfunction "2_2") (pintype "passive"))
      (node (ref "U1") (pin "8") (pinfunction "IO11_8") (pintype "passive"))
    )
    (net (code "41") (name "/SD_DATA0") (class "Default")
      (node (ref "CARD1") (pin "7") (pinfunction "DAT0_7") (pintype "passive"))
      (node (ref "R5") (pin "2") (pinfunction "2_2") (pintype "passive"))
      (node (ref "U1") (pin "39") (pinfunction "IO45_39") (pintype "passive"))
    )
    (net (code "42") (name "/SD_DATA1") (class "Default")
      (node (ref "CARD1") (pin "8") (pinfunction "DAT1_8") (pintype "passive"))
      (node (ref "R7") (pin "2") (pinfunction "2_2") (pintype "passive"))
      (node (ref "U1") (pin "25") (pinfunction "IO48_25") (pintype "passive"))
    )
    (net (code "43") (name "/SD_DATA2") (class "Default")
      (node (ref "CARD1") (pin "1") (pinfunction "DATA2_1") (pintype "passive"))
      (node (ref "R10") (pin "2") (pinfunction "2_2") (pintype "passive"))
      (node (ref "U1") (pin "34") (pinfunction "IO40_34") (pintype "passive"))
    )
    (net (code "44") (name "/SD_DATA3") (class "Default")
      (node (ref "CARD1") (pin "2") (pinfunction "CD/DATA3_2") (pintype "passive"))
      (node (ref "R12") (pin "2") (pinfunction "2_2") (pintype "passive"))
      (node (ref "U1") (pin "24") (pinfunction "IO21_24") (pintype "passive"))
    )
    (net (code "45") (name "/SD_SCLK") (class "Default")
      (node (ref "CARD1") (pin "5") (pinfunction "CLK_5") (pintype "passive"))
      (node (ref "U1") (pin "9") (pinfunction "IO13_9") (pintype "passive"))
    )
    (net (code "46") (name "/TE") (class "Default")
      (node (ref "FPC1") (pin "2") (pinfunction "2_2") (pintype "passive+no_connect"))
    )
    (net (code "47") (name "/U0RX") (class "Default")
      (node (ref "CN1") (pin "2") (pinfunction "2_2") (pintype "passive"))
      (node (ref "U1") (pin "38") (pinfunction "U0RX_38") (pintype "passive"))
      (node (ref "U2") (pin "2") (pinfunction "TXD_2") (pintype "passive"))
    )
    (net (code "48") (name "/U0TX") (class "Default")
      (node (ref "CN1") (pin "1") (pinfunction "1_1") (pintype "passive"))
      (node (ref "U1") (pin "37") (pinfunction "U0TX_37") (pintype "passive"))
      (node (ref "U2") (pin "3") (pinfunction "RXD_3") (pintype "passive"))
    )
    (net (code "49") (name "/WRX") (class "Default")
      (node (ref "FPC1") (pin "36") (pinfunction "36_36") (pintype "passive"))
      (node (ref "U1") (pin "15") (pinfunction "IO12_15") (pintype "passive"))
    )
    (net (code "50") (name "/XL") (class "Default")
      (node (ref "FPC1") (pin "46") (pinfunction "46_46") (pintype "passive+no_connect"))
    )
    (net (code "51") (name "/XR") (class "Default")
      (node (ref "FPC1") (pin "48") (pinfunction "48_48") (pintype "passive+no_connect"))
    )
    (net (code "52") (name "/YD") (class "Default")
      (node (ref "FPC1") (pin "47") (pinfunction "47_47") (pintype "passive+no_connect"))
    )
    (net (code "53") (name "/YU") (class "Default")
      (node (ref "FPC1") (pin "49") (pinfunction "49_49") (pintype "passive+no_connect"))
    )
    (net (code "54") (name "BAT+") (class "Default")
      (node (ref "C15") (pin "2") (pinfunction "2_2") (pintype "passive"))
      (node (ref "H2") (pin "1") (pinfunction "1_1") (pintype "passive"))
      (node (ref "L3") (pin "2") (pinfunction "2_2") (pintype "passive"))
      (node (ref "R25") (pin "1") (pinfunction "1_1") (pintype "passive"))
    )
    (net (code "55") (name "BAT_5V") (class "Default")
      (node (ref "C10") (pin "2") (pinfunction "2_2") (pintype "passive"))
      (node (ref "C11") (pin "2") (pinfunction "2_2") (pintype "passive"))
      (node (ref "SW1") (pin "2") (pinfunction "2_2") (pintype "passive"))
      (node (ref "U6") (pin "8") (pinfunction "VOUT_8") (pintype "passive"))
    )
    (net (code "56") (name "GND") (class "Default")
      (node (ref "BUZZER1") (pin "3") (pinfunction "3_3") (pintype "passive"))
      (node (ref "BUZZER1") (pin "4") (pinfunction "4_4") (pintype "passive"))
      (node (ref "C1") (pin "2") (pinfunction "2_2") (pintype "passive"))
      (node (ref "C10") (pin "1") (pinfunction "1_1") (pintype "passive"))
      (node (ref "C11") (pin "1") (pinfunction "1_1") (pintype "passive"))
      (node (ref "C12") (pin "2") (pinfunction "2_2") (pintype "passive"))
      (node (ref "C13") (pin "1") (pinfunction "1_1") (pintype "passive"))
      (node (ref "C14") (pin "1") (pinfunction "1_1") (pintype "passive"))
      (node (ref "C15") (pin "1") (pinfunction "1_1") (pintype "passive"))
      (node (ref "C16") (pin "1") (pinfunction "1_1") (pintype "passive"))
      (node (ref "C17") (pin "2") (pinfunction "2_2") (pintype "passive"))
      (node (ref "C2") (pin "2") (pinfunction "2_2") (pintype "passive"))
      (node (ref "C3") (pin "1") (pinfunction "1_1") (pintype "passive"))
      (node (ref "C4") (pin "1") (pinfunction "1_1") (pintype "passive"))
      (node (ref "C5") (pin "2") (pinfunction "2_2") (pintype "passive"))
      (node (ref "C6") (pin "2") (pinfunction "2_2") (pintype "passive"))
      (node (ref "C7") (pin "1") (pinfunction "1_1") (pintype "passive"))
      (node (ref "C9") (pin "2") (pinfunction "2_2") (pintype "passive"))
      (node (ref "CARD1") (pin "10") (pinfunction "GND_10") (pintype "passive"))
      (node (ref "CARD1") (pin "11") (pinfunction "GND_11") (pintype "passive"))
      (node (ref "CARD1") (pin "12") (pinfunction "GND_12") (pintype "passive"))
      (node (ref "CARD1") (pin "13") (pinfunction "GND_13") (pintype "passive"))
      (node (ref "CARD1") (pin "6") (pinfunction "VSS_6") (pintype "passive"))
      (node (ref "CN1") (pin "3") (pinfunction "3_3") (pintype "passive"))
      (node (ref "CN1") (pin "5") (pinfunction "5_5") (pintype "passive"))
      (node (ref "CN1") (pin "6") (pinfunction "6_6") (pintype "passive"))
      (node (ref "CN2") (pin "3") (pinfunction "3_3") (pintype "passive"))
      (node (ref "CN2") (pin "5") (pinfunction "5_5") (pintype "passive"))
      (node (ref "CN2") (pin "6") (pinfunction "6_6") (pintype "passive"))
      (node (ref "FPC1") (pin "17") (pinfunction "17_17") (pintype "passive"))
      (node (ref "FPC1") (pin "18") (pinfunction "18_18") (pintype "passive"))
      (node (ref "FPC1") (pin "19") (pinfunction "19_19") (pintype "passive"))
      (node (ref "FPC1") (pin "20") (pinfunction "20_20") (pintype "passive"))
      (node (ref "FPC1") (pin "21") (pinfunction "21_21") (pintype "passive"))
      (node (ref "FPC1") (pin "22") (pinfunction "22_22") (pintype "passive"))
      (node (ref "FPC1") (pin "23") (pinfunction "23_23") (pintype "passive"))
      (node (ref "FPC1") (pin "24") (pinfunction "24_24") (pintype "passive"))
      (node (ref "FPC1") (pin "25") (pinfunction "25_25") (pintype "passive"))
      (node (ref "FPC1") (pin "26") (pinfunction "26_26") (pintype "passive"))
      (node (ref "FPC1") (pin "27") (pinfunction "27_27") (pintype "passive"))
      (node (ref "FPC1") (pin "28") (pinfunction "28_28") (pintype "passive"))
      (node (ref "FPC1") (pin "29") (pinfunction "29_29") (pintype "passive"))
      (node (ref "FPC1") (pin "3") (pinfunction "3_3") (pintype "passive"))
      (node (ref "FPC1") (pin "30") (pinfunction "30_30") (pintype "passive"))
      (node (ref "FPC1") (pin "31") (pinfunction "31_31") (pintype "passive"))
      (node (ref "FPC1") (pin "32") (pinfunction "32_32") (pintype "passive"))
      (node (ref "FPC1") (pin "38") (pinfunction "38_38") (pintype "passive"))
      (node (ref "FPC1") (pin "4") (pinfunction "4_4") (pintype "passive"))
      (node (ref "FPC1") (pin "40") (pinfunction "40_40") (pintype "passive"))
      (node (ref "FPC1") (pin "41") (pinfunction "41_41") (pintype "passive"))
      (node (ref "FPC1") (pin "42") (pinfunction "42_42") (pintype "passive"))
      (node (ref "FPC1") (pin "43") (pinfunction "43_43") (pintype "passive"))
      (node (ref "FPC1") (pin "5") (pinfunction "5_5") (pintype "passive"))
      (node (ref "FPC1") (pin "52") (pinfunction "52_52") (pintype "passive"))
      (node (ref "FPC1") (pin "53") (pinfunction "53_53") (pintype "passive"))
      (node (ref "FPC1") (pin "6") (pinfunction "6_6") (pintype "passive"))
      (node (ref "FPC1") (pin "7") (pinfunction "7_7") (pintype "passive"))
      (node (ref "FPC1") (pin "8") (pinfunction "8_8") (pintype "passive"))
      (node (ref "H2") (pin "2") (pinfunction "2_2") (pintype "passive"))
      (node (ref "LED1") (pin "1") (pinfunction "C_1") (pintype "passive"))
      (node (ref "Q1") (pin "2") (pinfunction "S_2") (pintype "passive"))
      (node (ref "R11") (pin "1") (pinfunction "1_1") (pintype "passive"))
      (node (ref "R13") (pin "1") (pinfunction "1_1") (pintype "passive"))
      (node (ref "R16") (pin "1") (pinfunction "1_1") (pintype "passive"))
      (node (ref "R17") (pin "1") (pinfunction "1_1") (pintype "passive"))
      (node (ref "R18") (pin "1") (pinfunction "1_1") (pintype "passive"))
      (node (ref "R26") (pin "1") (pinfunction "1_1") (pintype "passive"))
      (node (ref "R4") (pin "1") (pinfunction "1_1") (pintype "passive"))
      (node (ref "R6") (pin "1") (pinfunction "1_1") (pintype "passive"))
      (node (ref "R8") (pin "1") (pinfunction "1_1") (pintype "passive"))
      (node (ref "SW2") (pin "4") (pinfunction "4_4") (pintype "passive"))
      (node (ref "SW3") (pin "1") (pinfunction "1_1") (pintype "passive"))
      (node (ref "SW3") (pin "2") (pinfunction "2_2") (pintype "passive"))
      (node (ref "SW3") (pin "4") (pinfunction "4_4") (pintype "passive"))
      (node (ref "SW4") (pin "1") (pinfunction "1_1") (pintype "passive"))
      (node (ref "SW4") (pin "2") (pinfunction "2_2") (pintype "passive"))
      (node (ref "SW4") (pin "4") (pinfunction "4_4") (pintype "passive"))
      (node (ref "SW5") (pin "1") (pinfunction "1_1") (pintype "passive"))
      (node (ref "SW5") (pin "2") (pinfunction "2_2") (pintype "passive"))
      (node (ref "SW5") (pin "4") (pinfunction "4_4") (pintype "passive"))
      (node (ref "SW6") (pin "1") (pinfunction "1_1") (pintype "passive"))
      (node (ref "SW6") (pin "2") (pinfunction "2_2") (pintype "passive"))
      (node (ref "SW6") (pin "4") (pinfunction "4_4") (pintype "passive"))
      (node (ref "U1") (pin "1") (pinfunction "GND_1") (pintype "passive"))
      (node (ref "U1") (pin "26") (pinfunction "GND_26") (pintype "passive"))
      (node (ref "U1") (pin "42") (pinfunction "GND_42") (pintype "passive"))
      (node (ref "U2") (pin "1") (pinfunction "GND_1") (pintype "passive"))
      (node (ref "U3") (pin "2") (pinfunction "GND_2") (pintype "passive"))
      (node (ref "U5") (pin "2") (pinfunction "GND_2") (pintype "passive"))
      (node (ref "U6") (pin "9") (pinfunction "EP_9") (pintype "passive"))
      (node (ref "U7") (pin "5") (pinfunction "GND_5") (pintype "passive"))
      (node (ref "USB1") (pin "1") (pinfunction "EH_1") (pintype "passive"))
      (node (ref "USB1") (pin "A1") (pinfunction "GND_A1") (pintype "passive"))
      (node (ref "USB1") (pin "A12") (pinfunction "GND_A12") (pintype "passive"))
      (node (ref "USB2") (pin "1") (pinfunction "EH_1") (pintype "passive"))
      (node (ref "USB2") (pin "A1") (pinfunction "GND_A1") (pintype "passive"))
      (node (ref "USB2") (pin "A12") (pinfunction "GND_A12") (pintype "passive"))
    )
    (net (code "57") (name "Net-(C14-Pad2)") (class "Default")
      (node (ref "C14") (pin "2") (pinfunction "2_2") (pintype "passive"))
      (node (ref "R24") (pin "1") (pinfunction "1_1") (pintype "passive"))
    )
    (net (code "58") (name "Net-(D1-A)") (class "Default")
      (node (ref "BUZZER1") (pin "2") (pinfunction "2_2") (pintype "passive"))
      (node (ref "D1") (pin "2") (pinfunction "A_2") (pintype "passive"))
      (node (ref "Q1") (pin "3") (pinfunction "D_3") (pintype "passive"))
    )
    (net (code "59") (name "Net-(D2-A)") (class "Default")
      (node (ref "D2") (pin "2") (pinfunction "A_2") (pintype "passive"))
      (node (ref "L1") (pin "1") (pinfunction "1_1") (pintype "passive"))
      (node (ref "U3") (pin "1") (pinfunction "LX_1") (pintype "passive"))
    )
    (net (code "60") (name "Net-(LED1-A)") (class "Default")
      (node (ref "LED1") (pin "2") (pinfunction "A_2") (pintype "passive"))
      (node (ref "R1") (pin "1") (pinfunction "1_1") (pintype "passive"))
    )
    (net (code "61") (name "Net-(LED4-A)") (class "Default")
      (node (ref "LED4") (pin "2") (pinfunction "A_2") (pintype "passive"))
      (node (ref "LED5") (pin "1") (pinfunction "C_1") (pintype "passive"))
      (node (ref "LED6") (pin "2") (pinfunction "A_2") (pintype "passive"))
      (node (ref "LED7") (pin "1") (pinfunction "C_1") (pintype "passive"))
      (node (ref "R27") (pin "2") (pinfunction "2_2") (pintype "passive"))
    )
    (net (code "62") (name "Net-(LED4-C)") (class "Default")
      (node (ref "LED4") (pin "1") (pinfunction "C_1") (pintype "passive"))
      (node (ref "LED7") (pin "2") (pinfunction "A_2") (pintype "passive"))
      (node (ref "U6") (pin "3") (pinfunction "LED2_3") (pintype "passive"))
    )
    (net (code "63") (name "Net-(LED5-A)") (class "Default")
      (node (ref "LED5") (pin "2") (pinfunction "A_2") (pintype "passive"))
      (node (ref "LED6") (pin "1") (pinfunction "C_1") (pintype "passive"))
      (node (ref "U6") (pin "2") (pinfunction "LED1_2") (pintype "passive"))
    )
    (net (code "64") (name "Net-(Q1-G)") (class "Default")
      (node (ref "Q1") (pin "1") (pinfunction "G_1") (pintype "passive"))
      (node (ref "R3") (pin "2") (pinfunction "2_2") (pintype "passive"))
      (node (ref "R4") (pin "2") (pinfunction "2_2") (pintype "passive"))
    )
    (net (code "65") (name "Net-(R28-Pad2)") (class "Default")
      (node (ref "R28") (pin "2") (pinfunction "2_2") (pintype "passive"))
      (node (ref "SW2") (pin "3") (pinfunction "3_3") (pintype "passive"))
    )
    (net (code "66") (name "Net-(U6-BAT)") (class "Default")
      (node (ref "C16") (pin "2") (pinfunction "2_2") (pintype "passive"))
      (node (ref "R25") (pin "2") (pinfunction "2_2") (pintype "passive"))
      (node (ref "U6") (pin "6") (pinfunction "BAT_6") (pintype "passive"))
    )
    (net (code "67") (name "Net-(U6-KEY)") (class "Default")
      (node (ref "R28") (pin "1") (pinfunction "1_1") (pintype "passive"))
      (node (ref "U6") (pin "5") (pinfunction "KEY_5") (pintype "passive"))
    )
    (net (code "68") (name "Net-(U6-LED3)") (class "Default")
      (node (ref "R27") (pin "1") (pinfunction "1_1") (pintype "passive"))
      (node (ref "U6") (pin "4") (pinfunction "LED3_4") (pintype "passive"))
    )
    (net (code "69") (name "Net-(U6-SW)") (class "Default")
      (node (ref "L3") (pin "1") (pinfunction "1_1") (pintype "passive"))
      (node (ref "U6") (pin "7") (pinfunction "SW_7") (pintype "passive"))
    )
    (net (code "70") (name "VBUS") (class "Default")
      (node (ref "C13") (pin "2") (pinfunction "2_2") (pintype "passive"))
      (node (ref "R24") (pin "2") (pinfunction "2_2") (pintype "passive"))
      (node (ref "U6") (pin "1") (pinfunction "VIN_1") (pintype "passive"))
      (node (ref "USB1") (pin "A11") (pinfunction "VBUS_A11") (pintype "passive"))
      (node (ref "USB1") (pin "A2") (pinfunction "VBUS_A2") (pintype "passive"))
      (node (ref "USB2") (pin "A11") (pinfunction "VBUS_A11") (pintype "passive"))
      (node (ref "USB2") (pin "A2") (pinfunction "VBUS_A2") (pintype "passive"))
    )
    (net (code "71") (name "VCC") (class "Default")
      (node (ref "BUZZER1") (pin "1") (pinfunction "+_1") (pintype "passive"))
      (node (ref "C1") (pin "1") (pinfunction "1_1") (pintype "passive"))
      (node (ref "C12") (pin "1") (pinfunction "1_1") (pintype "passive"))
      (node (ref "C2") (pin "1") (pinfunction "1_1") (pintype "passive"))
      (node (ref "C7") (pin "2") (pinfunction "2_2") (pintype "passive"))
      (node (ref "C8") (pin "2") (pinfunction "2_2") (pintype "passive"))
      (node (ref "CARD1") (pin "4") (pinfunction "VDD_4") (pintype "passive"))
      (node (ref "CN1") (pin "4") (pinfunction "4_4") (pintype "passive"))
      (node (ref "CN2") (pin "4") (pinfunction "4_4") (pintype "passive"))
      (node (ref "D1") (pin "1") (pinfunction "C_1") (pintype "passive"))
      (node (ref "FPC1") (pin "35") (pinfunction "35_35") (pintype "passive"))
      (node (ref "FPC1") (pin "44") (pinfunction "44_44") (pintype "passive"))
      (node (ref "FPC1") (pin "45") (pinfunction "45_45") (pintype "passive"))
      (node (ref "L2") (pin "1") (pinfunction "1_1") (pintype "passive"))
      (node (ref "R10") (pin "1") (pinfunction "1_1") (pintype "passive"))
      (node (ref "R12") (pin "1") (pinfunction "1_1") (pintype "passive"))
      (node (ref "R14") (pin "1") (pinfunction "1_1") (pintype "passive"))
      (node (ref "R2") (pin "2") (pinfunction "2_2") (pintype "passive"))
      (node (ref "R23") (pin "1") (pinfunction "1_1") (pintype "passive"))
      (node (ref "R5") (pin "1") (pinfunction "1_1") (pintype "passive"))
      (node (ref "R7") (pin "1") (pinfunction "1_1") (pintype "passive"))
      (node (ref "U1") (pin "2") (pinfunction "VCC_2") (pintype "passive"))
      (node (ref "U2") (pin "16") (pinfunction "VCC_16") (pintype "passive"))
      (node (ref "U2") (pin "4") (pinfunction "V3_4") (pintype "passive"))
      (node (ref "U7") (pin "2") (pinfunction "VDD_2") (pintype "passive"))
    )
    (net (code "72") (name "VCC_5V") (class "Default")
      (node (ref "C6") (pin "1") (pinfunction "1_1") (pintype "passive"))
      (node (ref "C9") (pin "1") (pinfunction "1_1") (pintype "passive"))
      (node (ref "L1") (pin "2") (pinfunction "2_2") (pintype "passive"))
      (node (ref "R1") (pin "2") (pinfunction "2_2") (pintype "passive"))
      (node (ref "R15") (pin "2") (pinfunction "2_2") (pintype "passive"))
      (node (ref "SW1") (pin "3") (pinfunction "3_3") (pintype "passive"))
      (node (ref "U3") (pin "6") (pinfunction "IN_6") (pintype "passive"))
      (node (ref "U5") (pin "1") (pinfunction "EN_1") (pintype "passive"))
      (node (ref "U5") (pin "4") (pinfunction "IN_4") (pintype "passive"))
    )
    (net (code "73") (name "unconnected-(CARD1-CD-Pad9)") (class "Default")
      (node (ref "CARD1") (pin "9") (pinfunction "CD_9") (pintype "passive+no_connect"))
    )
    (net (code "74") (name "unconnected-(SW1-Pad1)") (class "Default")
      (node (ref "SW1") (pin "1") (pinfunction "1_1") (pintype "passive+no_connect"))
    )
    (net (code "75") (name "unconnected-(SW1-Pad4)") (class "Default")
      (node (ref "SW1") (pin "4") (pinfunction "4_4") (pintype "passive+no_connect"))
    )
    (net (code "76") (name "unconnected-(SW1-Pad5)") (class "Default")
      (node (ref "SW1") (pin "5") (pinfunction "5_5") (pintype "passive+no_connect"))
    )
    (net (code "77") (name "unconnected-(SW2-Pad1)") (class "Default")
      (node (ref "SW2") (pin "1") (pinfunction "1_1") (pintype "passive+no_connect"))
    )
    (net (code "78") (name "unconnected-(SW2-Pad2)") (class "Default")
      (node (ref "SW2") (pin "2") (pinfunction "2_2") (pintype "passive+no_connect"))
    )
    (net (code "79") (name "unconnected-(U1-IO35-Pad29)") (class "Default")
      (node (ref "U1") (pin "29") (pinfunction "IO35_29") (pintype "passive+no_connect"))
    )
    (net (code "80") (name "unconnected-(U1-IO36-Pad30)") (class "Default")
      (node (ref "U1") (pin "30") (pinfunction "IO36_30") (pintype "passive+no_connect"))
    )
    (net (code "81") (name "unconnected-(U1-IO37-Pad31)") (class "Default")
      (node (ref "U1") (pin "31") (pinfunction "IO37_31") (pintype "passive+no_connect"))
    )
    (net (code "82") (name "unconnected-(U1-IO46-Pad40)") (class "Default")
      (node (ref "U1") (pin "40") (pinfunction "IO46_40") (pintype "passive+no_connect"))
    )
    (net (code "83") (name "unconnected-(U2-CTS#-Pad9)") (class "Default")
      (node (ref "U2") (pin "9") (pinfunction "CTS#_9") (pintype "passive+no_connect"))
    )
    (net (code "84") (name "unconnected-(U2-DCD#-Pad12)") (class "Default")
      (node (ref "U2") (pin "12") (pinfunction "DCD#_12") (pintype "passive+no_connect"))
    )
    (net (code "85") (name "unconnected-(U2-DSR#-Pad10)") (class "Default")
      (node (ref "U2") (pin "10") (pinfunction "DSR#_10") (pintype "passive+no_connect"))
    )
    (net (code "86") (name "unconnected-(U2-NC.-Pad7)") (class "Default")
      (node (ref "U2") (pin "7") (pinfunction "NC._7") (pintype "passive+no_connect"))
    )
    (net (code "87") (name "unconnected-(U2-NC.-Pad8)") (class "Default")
      (node (ref "U2") (pin "8") (pinfunction "NC._8") (pintype "passive+no_connect"))
    )
    (net (code "88") (name "unconnected-(U2-R232-Pad15)") (class "Default")
      (node (ref "U2") (pin "15") (pinfunction "R232_15") (pintype "passive+no_connect"))
    )
    (net (code "89") (name "unconnected-(U2-RI#-Pad11)") (class "Default")
      (node (ref "U2") (pin "11") (pinfunction "RI#_11") (pintype "passive+no_connect"))
    )
    (net (code "90") (name "unconnected-(U7-NC-Pad1)") (class "Default")
      (node (ref "U7") (pin "1") (pinfunction "NC_1") (pintype "passive+no_connect"))
    )
    (net (code "91") (name "unconnected-(U7-NC-Pad6)") (class "Default")
      (node (ref "U7") (pin "6") (pinfunction "NC_6") (pintype "passive+no_connect"))
    )
    (net (code "92") (name "unconnected-(USB1-SBU1-PadA9)") (class "Default")
      (node (ref "USB1") (pin "A9") (pinfunction "SBU1_A9") (pintype "passive+no_connect"))
    )
    (net (code "93") (name "unconnected-(USB1-SBU2-PadA3)") (class "Default")
      (node (ref "USB1") (pin "A3") (pinfunction "SBU2_A3") (pintype "passive+no_connect"))
    )
    (net (code "94") (name "unconnected-(USB2-SBU1-PadA9)") (class "Default")
      (node (ref "USB2") (pin "A9") (pinfunction "SBU1_A9") (pintype "passive+no_connect"))
    )
    (net (code "95") (name "unconnected-(USB2-SBU2-PadA3)") (class "Default")
      (node (ref "USB2") (pin "A3") (pinfunction "SBU2_A3") (pintype "passive+no_connect"))
    )
  )
)
